# ProProject_Turbo_Drive_2024-05-30.net
KiCad netlist of a schematic drawn in EasyEDA Pro
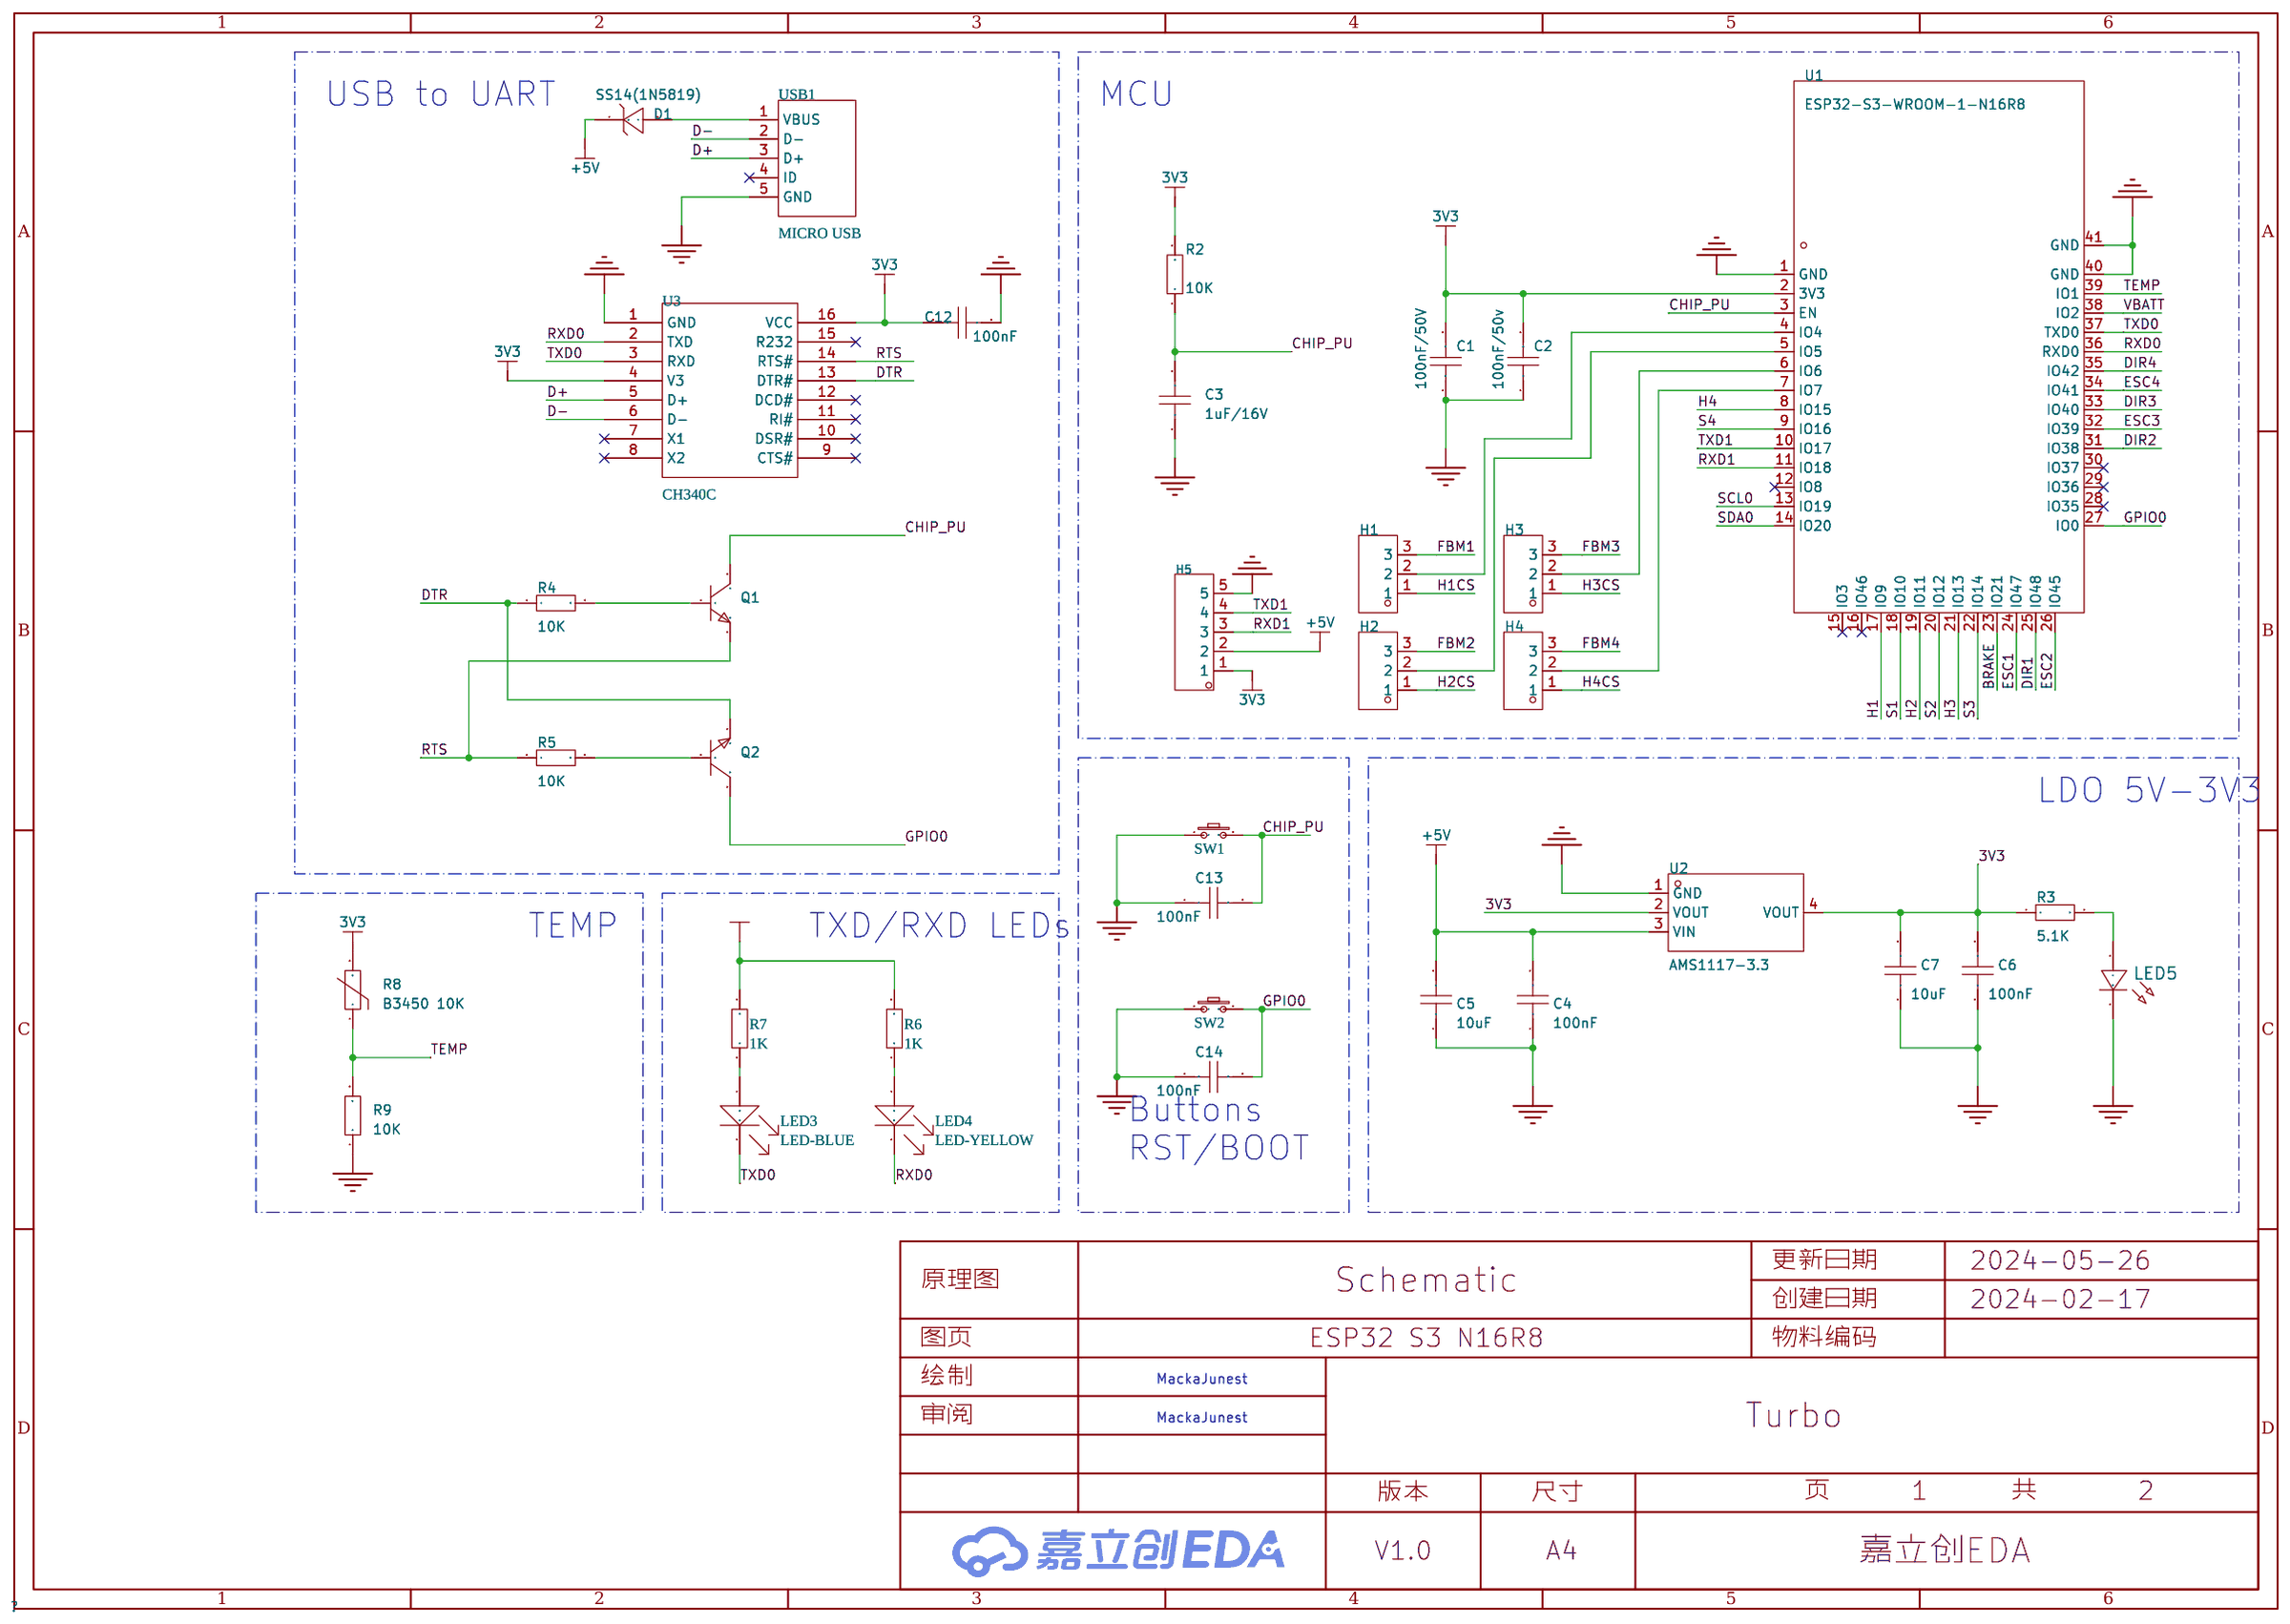
[diagram p0: ESP32 S3 N16R8]
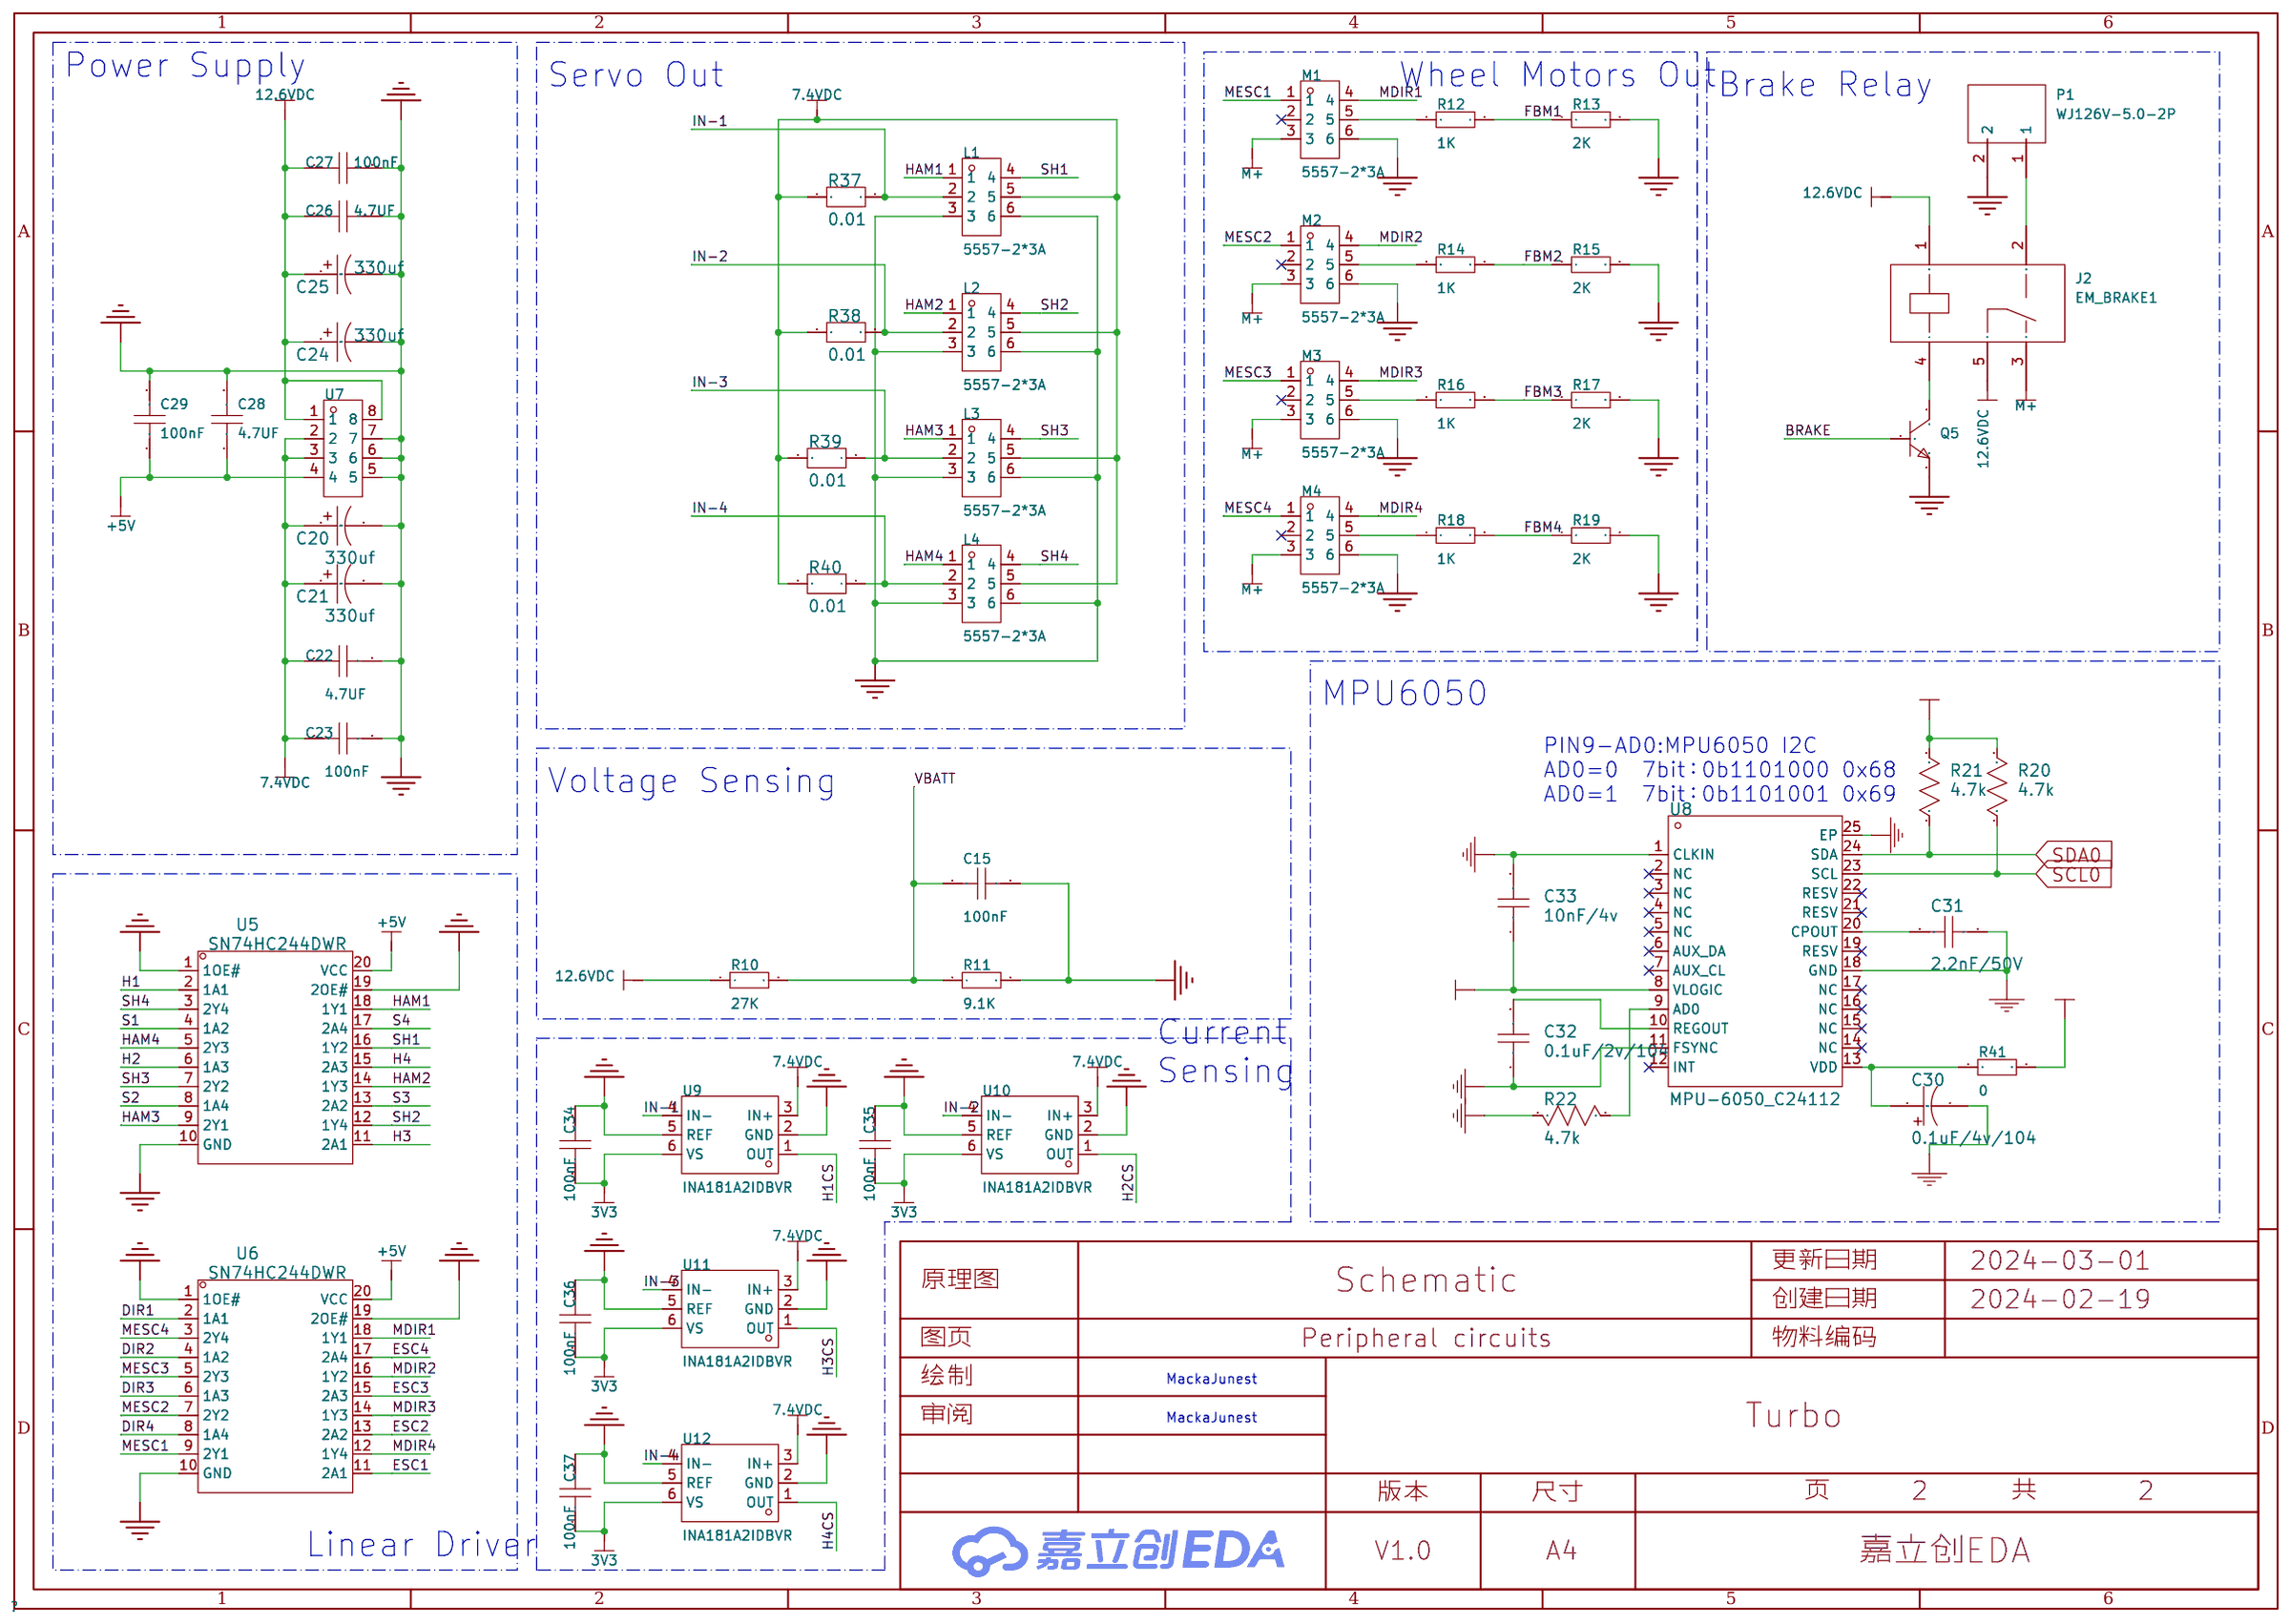
[diagram p1: Peripheral circuits]

(export (version "E")
  (design (tool "Eeschema 10.0.6"))
  (components
    (comp (ref "C1")
      (value "100nF/50V")
      (footprint "easyedapro:C0603")
      (libsource (lib "easyedapro") (part "CapAcitance"))
    )
    (comp (ref "C2")
      (value "100nF/50v")
      (footprint "easyedapro:C0603")
      (libsource (lib "easyedapro") (part "CapAcitance"))
    )
    (comp (ref "C3")
      (value "1uF/16V")
      (footprint "easyedapro:C0603")
      (libsource (lib "easyedapro") (part "CapAcitance"))
    )
    (comp (ref "C4")
      (value "100nF")
      (footprint "easyedapro:C0603")
      (libsource (lib "easyedapro") (part "CapAcitance"))
    )
    (comp (ref "C5")
      (value "10uF")
      (footprint "easyedapro:C0603")
      (libsource (lib "easyedapro") (part "CapAcitance"))
    )
    (comp (ref "C6")
      (value "100nF")
      (footprint "easyedapro:C0603")
      (libsource (lib "easyedapro") (part "CapAcitance"))
    )
    (comp (ref "C7")
      (value "10uF")
      (footprint "easyedapro:C0603")
      (libsource (lib "easyedapro") (part "CapAcitance"))
    )
    (comp (ref "C12")
      (value "100nF")
      (footprint "easyedapro:C0603")
      (libsource (lib "easyedapro") (part "CapAcitance"))
    )
    (comp (ref "C13")
      (value "100nF")
      (footprint "easyedapro:C0603")
      (libsource (lib "easyedapro") (part "CapAcitance"))
    )
    (comp (ref "C14")
      (value "100nF")
      (footprint "easyedapro:C0603")
      (libsource (lib "easyedapro") (part "CapAcitance"))
    )
    (comp (ref "D1")
      (value "SS14(1N5819)")
      (footprint "easyedapro:SMA_L4.3-W2.7-LS5.1-RD")
      (libsource (lib "easyedapro") (part "SS14(1N5819)-SMA"))
    )
    (comp (ref "H1")
      (value "~")
      (footprint "easyedapro:HDR-TH_3P-P2.54-V-M")
      (libsource (lib "easyedapro") (part "PZ254V-11-03P_C2937625"))
    )
    (comp (ref "H2")
      (value "~")
      (footprint "easyedapro:HDR-TH_3P-P2.54-V-M")
      (libsource (lib "easyedapro") (part "PZ254V-11-03P_C2937625"))
    )
    (comp (ref "H3")
      (value "~")
      (footprint "easyedapro:HDR-TH_3P-P2.54-V-M")
      (libsource (lib "easyedapro") (part "PZ254V-11-03P_C2937625"))
    )
    (comp (ref "H4")
      (value "~")
      (footprint "easyedapro:HDR-TH_3P-P2.54-V-M")
      (libsource (lib "easyedapro") (part "PZ254V-11-03P_C2937625"))
    )
    (comp (ref "H5")
      (value "~")
      (footprint "easyedapro:HDR-TH_5P-P2.54-V-M")
      (libsource (lib "easyedapro") (part "MTP125-1105S1"))
    )
    (comp (ref "LED3")
      (value "LED-BLUE")
      (footprint "easyedapro:LED 0805B")
      (libsource (lib "easyedapro") (part "LED-BLUE"))
    )
    (comp (ref "LED4")
      (value "LED-YELLOW")
      (footprint "easyedapro:LED 0805Y")
      (libsource (lib "easyedapro") (part "LED-YELLOW"))
    )
    (comp (ref "LED5")
      (value "~")
      (footprint "easyedapro:LED_0603")
      (libsource (lib "easyedapro") (part "LED_R"))
    )
    (comp (ref "Q1")
      (value "~")
      (footprint "easyedapro:S8050_SOT-23")
      (libsource (lib "easyedapro") (part "NPN"))
    )
    (comp (ref "Q2")
      (value "~")
      (footprint "easyedapro:S8050_SOT-23")
      (libsource (lib "easyedapro") (part "NPN"))
    )
    (comp (ref "R2") (value "10K") (footprint "easyedapro:R0603") (libsource (lib "easyedapro") (part "电阻")))
    (comp (ref "R3") (value "5.1K") (footprint "easyedapro:R0603") (libsource (lib "easyedapro") (part "电阻")))
    (comp (ref "R4") (value "10K") (footprint "easyedapro:R0603") (libsource (lib "easyedapro") (part "电阻")))
    (comp (ref "R5") (value "10K") (footprint "easyedapro:R0603") (libsource (lib "easyedapro") (part "电阻")))
    (comp (ref "R6")
      (value "1K")
      (footprint "easyedapro:R 0603_L")
      (libsource (lib "easyedapro") (part "1K"))
    )
    (comp (ref "R7")
      (value "1K")
      (footprint "easyedapro:R 0603_L")
      (libsource (lib "easyedapro") (part "1K"))
    )
    (comp (ref "R8")
      (value "B3450 10K")
      (footprint "easyedapro:R0603")
      (description "阻值(25°C):10kΩ;B值(25°C/50°C):3950K;电阻精度:±1%;功率:100mW;B值精度:±1%;最大稳态电流(25°C):310uA;")
      (fields (field (name "Manufacturer") "KUU"))
      (libsource (lib "easyedapro") (part "KNTC0603/10KF3950"))
    )
    (comp (ref "R9") (value "10K") (footprint "easyedapro:R0603") (libsource (lib "easyedapro") (part "电阻")))
    (comp (ref "SW1")
      (value "3x6x5")
      (footprint "easyedapro:TSW SMD-3*6*2.5")
      (libsource (lib "easyedapro") (part "3x6x5"))
    )
    (comp (ref "SW2")
      (value "3x6x5")
      (footprint "easyedapro:TSW SMD-3*6*2.5")
      (libsource (lib "easyedapro") (part "3x6x5"))
    )
    (comp (ref "U1")
      (value "ESP32-S3-WROOM-1-N16R8")
      (footprint "easyedapro:WIRELM-SMD_ESP32-S3-WROOM-1")
      (fields (field (name "Manufacturer") "ESPRESSIF(乐鑫)"))
      (libsource (lib "easyedapro") (part "ESP32-S3-WROOM-1(N16R8)"))
    )
    (comp (ref "U2")
      (value "AMS1117-3.3")
      (footprint "easyedapro:SOT-223-3_L6.5-W3.4-P2.30-LS7.0-BR")
      (description "输出类型:固定;最大输入电压:-;输出电压:3.3V;最大输出电流:1A;电源纹波抑制比(PSRR):72dB@(120Hz);输出极性:正极;")
      (fields (field (name "Manufacturer") "AMS"))
      (libsource (lib "easyedapro") (part "AMS1117-3.3"))
    )
    (comp (ref "U3")
      (value "CH340C")
      (footprint "easyedapro:SOP16_L")
      (libsource (lib "easyedapro") (part "CH340C"))
    )
    (comp (ref "USB1")
      (value "MICRO USB")
      (footprint "easyedapro:USB-MICRO_B")
      (libsource (lib "easyedapro") (part "MICRO USB"))
    )
    (comp (ref "C15")
      (value "100nF")
      (footprint "easyedapro:C0603")
      (libsource (lib "easyedapro") (part "CapAcitance"))
    )
    (comp (ref "C20")
      (value "330uf")
      (footprint "easyedapro:CAP-T-10*10.5")
      (libsource (lib "easyedapro") (part "330uf"))
    )
    (comp (ref "C21")
      (value "330uf")
      (footprint "easyedapro:CAP-T-10*10.5")
      (libsource (lib "easyedapro") (part "330uf"))
    )
    (comp (ref "C22")
      (value "4.7UF")
      (footprint "easyedapro:C0603")
      (libsource (lib "easyedapro") (part "CapAcitance"))
    )
    (comp (ref "C23")
      (value "100nF")
      (footprint "easyedapro:C0603")
      (libsource (lib "easyedapro") (part "CapAcitance"))
    )
    (comp (ref "C24")
      (value "330uf")
      (footprint "easyedapro:CAP-T-10*10.5")
      (libsource (lib "easyedapro") (part "330uf"))
    )
    (comp (ref "C25")
      (value "330uf")
      (footprint "easyedapro:CAP-T-10*10.5")
      (libsource (lib "easyedapro") (part "330uf"))
    )
    (comp (ref "C26")
      (value "4.7UF")
      (footprint "easyedapro:C0603")
      (libsource (lib "easyedapro") (part "CapAcitance"))
    )
    (comp (ref "C27")
      (value "100nF")
      (footprint "easyedapro:C0603")
      (libsource (lib "easyedapro") (part "CapAcitance"))
    )
    (comp (ref "C28")
      (value "4.7UF")
      (footprint "easyedapro:C0603")
      (libsource (lib "easyedapro") (part "CapAcitance"))
    )
    (comp (ref "C29")
      (value "100nF")
      (footprint "easyedapro:C0603")
      (libsource (lib "easyedapro") (part "CapAcitance"))
    )
    (comp (ref "C30")
      (value "0.1uF/4v/104")
      (fields (field (name "Manufacturer Part") "TPSA106K016R1000") (field (name "Manufacturer") "AVX"))
      (libsource (lib "easyedapro") (part "0.1uF/4v/104"))
    )
    (comp (ref "C31") (value "2.2nF/50V") (libsource (lib "easyedapro") (part "2.2nF/50V")))
    (comp (ref "C32") (value "0.1uF/2v/104") (libsource (lib "easyedapro") (part "0.1uF/2v/104")))
    (comp (ref "C33") (value "10nF/4v") (libsource (lib "easyedapro") (part "10nF/4v")))
    (comp (ref "C34")
      (value "100nF")
      (footprint "easyedapro:C0603")
      (libsource (lib "easyedapro") (part "CapAcitance"))
    )
    (comp (ref "C35")
      (value "100nF")
      (footprint "easyedapro:C0603")
      (libsource (lib "easyedapro") (part "CapAcitance"))
    )
    (comp (ref "C36")
      (value "100nF")
      (footprint "easyedapro:C0603")
      (libsource (lib "easyedapro") (part "CapAcitance"))
    )
    (comp (ref "C37")
      (value "100nF")
      (footprint "easyedapro:C0603")
      (libsource (lib "easyedapro") (part "CapAcitance"))
    )
    (comp (ref "J2")
      (value "EM_BRAKE1")
      (footprint "easyedapro:RELAY-TH_SRD-XXVDC-XL-C")
      (description "线圈电压:12V;触点形式:一组转换:1C(单刀双掷-转换);触点容量(电阻负载):-;最大切换电压:250V@AC;最大切换电流:15A;")
      (fields (field (name "Manufacturer Part") "SRD-12VDC-SL-C") (field (name "Manufacturer") "松乐"))
      (libsource (lib "easyedapro") (part "SRD-12VDC-SL-C"))
    )
    (comp (ref "L1")
      (value "5557-2*3A")
      (footprint "easyedapro:CONN-TH_5557-2X3A")
      (fields (field (name "Manufacturer") "FG(富港)"))
      (libsource (lib "easyedapro") (part "5557-2*3A"))
    )
    (comp (ref "L2")
      (value "5557-2*3A")
      (footprint "easyedapro:CONN-TH_5557-2X3A")
      (fields (field (name "Manufacturer") "FG(富港)"))
      (libsource (lib "easyedapro") (part "5557-2*3A"))
    )
    (comp (ref "L3")
      (value "5557-2*3A")
      (footprint "easyedapro:CONN-TH_5557-2X3A")
      (fields (field (name "Manufacturer") "FG(富港)"))
      (libsource (lib "easyedapro") (part "5557-2*3A"))
    )
    (comp (ref "L4")
      (value "5557-2*3A")
      (footprint "easyedapro:CONN-TH_5557-2X3A")
      (fields (field (name "Manufacturer") "FG(富港)"))
      (libsource (lib "easyedapro") (part "5557-2*3A"))
    )
    (comp (ref "M1")
      (value "5557-2*3A")
      (footprint "easyedapro:CONN-TH_5557-2X3A")
      (fields (field (name "Manufacturer") "FG(富港)"))
      (libsource (lib "easyedapro") (part "5557-2*3A"))
    )
    (comp (ref "M2")
      (value "5557-2*3A")
      (footprint "easyedapro:CONN-TH_5557-2X3A")
      (fields (field (name "Manufacturer") "FG(富港)"))
      (libsource (lib "easyedapro") (part "5557-2*3A"))
    )
    (comp (ref "M3")
      (value "5557-2*3A")
      (footprint "easyedapro:CONN-TH_5557-2X3A")
      (fields (field (name "Manufacturer") "FG(富港)"))
      (libsource (lib "easyedapro") (part "5557-2*3A"))
    )
    (comp (ref "M4")
      (value "5557-2*3A")
      (footprint "easyedapro:CONN-TH_5557-2X3A")
      (fields (field (name "Manufacturer") "FG(富港)"))
      (libsource (lib "easyedapro") (part "5557-2*3A"))
    )
    (comp (ref "P1")
      (value "WJ126V-5.0-2P")
      (footprint "easyedapro:CONN-TH_WJ126V-5.0-2P")
      (fields (field (name "Manufacturer") "KANGNEX(康奈克斯电气)"))
      (libsource (lib "easyedapro") (part "WJ126V-5.0-2P"))
    )
    (comp (ref "Q5")
      (value "~")
      (footprint "easyedapro:S8050_SOT-23")
      (libsource (lib "easyedapro") (part "NPN"))
    )
    (comp (ref "R10") (value "27K") (footprint "easyedapro:R0603") (libsource (lib "easyedapro") (part "电阻")))
    (comp (ref "R11")
      (value "9.1K")
      (footprint "easyedapro:R0603")
      (libsource (lib "easyedapro") (part "电阻"))
    )
    (comp (ref "R12") (value "1K") (footprint "easyedapro:R0603") (libsource (lib "easyedapro") (part "电阻")))
    (comp (ref "R13") (value "2K") (footprint "easyedapro:R0603") (libsource (lib "easyedapro") (part "电阻")))
    (comp (ref "R14") (value "1K") (footprint "easyedapro:R0603") (libsource (lib "easyedapro") (part "电阻")))
    (comp (ref "R15") (value "2K") (footprint "easyedapro:R0603") (libsource (lib "easyedapro") (part "电阻")))
    (comp (ref "R16") (value "1K") (footprint "easyedapro:R0603") (libsource (lib "easyedapro") (part "电阻")))
    (comp (ref "R17") (value "2K") (footprint "easyedapro:R0603") (libsource (lib "easyedapro") (part "电阻")))
    (comp (ref "R18") (value "1K") (footprint "easyedapro:R0603") (libsource (lib "easyedapro") (part "电阻")))
    (comp (ref "R19") (value "2K") (footprint "easyedapro:R0603") (libsource (lib "easyedapro") (part "电阻")))
    (comp (ref "R20") (value "4.7k") (libsource (lib "easyedapro") (part "4.7k")))
    (comp (ref "R21") (value "4.7k") (libsource (lib "easyedapro") (part "4.7k")))
    (comp (ref "R22") (value "4.7k") (libsource (lib "") (part "4.7k_1")))
    (comp (ref "R37")
      (value "0.01")
      (footprint "easyedapro:R2512")
      (libsource (lib "easyedapro") (part "0.01"))
    )
    (comp (ref "R38")
      (value "0.01")
      (footprint "easyedapro:R2512")
      (libsource (lib "easyedapro") (part "0.01"))
    )
    (comp (ref "R39")
      (value "0.01")
      (footprint "easyedapro:R2512")
      (libsource (lib "easyedapro") (part "0.01"))
    )
    (comp (ref "R40")
      (value "0.01")
      (footprint "easyedapro:R2512")
      (libsource (lib "easyedapro") (part "0.01"))
    )
    (comp (ref "R41") (value "0") (footprint "easyedapro:R0603") (libsource (lib "easyedapro") (part "电阻")))
    (comp (ref "U5")
      (value "SN74HC244DWR")
      (footprint "easyedapro:SOIC-20_L13.0-W7.6-P1.27-LS10.6-BL")
      (fields (field (name "Manufacturer Part") "SN74AHC244DWR") (field (name "Manufacturer") "TI"))
      (libsource (lib "easyedapro") (part "SN74HC244DWR"))
    )
    (comp (ref "U6")
      (value "SN74HC244DWR")
      (footprint "easyedapro:SOIC-20_L13.0-W7.6-P1.27-LS10.6-BL")
      (fields (field (name "Manufacturer Part") "SN74AHC244DWR") (field (name "Manufacturer") "TI"))
      (libsource (lib "easyedapro") (part "SN74HC244DWR"))
    )
    (comp (ref "U7")
      (value "5557-2*4P直针座-黑色8芯")
      (footprint "easyedapro:CONN-TH_5557-2-4P")
      (libsource (lib "easyedapro") (part "5557-2*4P直针座-黑色8芯"))
    )
    (comp (ref "U8")
      (value "MPU-6050_C24112")
      (fields (field (name "Manufacturer Part") "MPU-6050") (field (name "Manufacturer") "InvenSense"))
      (libsource (lib "easyedapro") (part "MPU-6050_C24112"))
    )
    (comp (ref "U9")
      (value "INA181A2IDBVR")
      (footprint "easyedapro:SOT-23-6_L2.9-W1.6-P0.95-LS2.8-BL")
      (description "放大器数:单路;")
      (fields (field (name "Manufacturer") "TI(德州仪器)"))
      (libsource (lib "easyedapro") (part "INA181A2IDBVR"))
    )
    (comp (ref "U10")
      (value "INA181A2IDBVR")
      (footprint "easyedapro:SOT-23-6_L2.9-W1.6-P0.95-LS2.8-BL")
      (description "放大器数:单路;")
      (fields (field (name "Manufacturer") "TI(德州仪器)"))
      (libsource (lib "easyedapro") (part "INA181A2IDBVR"))
    )
    (comp (ref "U11")
      (value "INA181A2IDBVR")
      (footprint "easyedapro:SOT-23-6_L2.9-W1.6-P0.95-LS2.8-BL")
      (description "放大器数:单路;")
      (fields (field (name "Manufacturer") "TI(德州仪器)"))
      (libsource (lib "easyedapro") (part "INA181A2IDBVR"))
    )
    (comp (ref "U12")
      (value "INA181A2IDBVR")
      (footprint "easyedapro:SOT-23-6_L2.9-W1.6-P0.95-LS2.8-BL")
      (description "放大器数:单路;")
      (fields (field (name "Manufacturer") "TI(德州仪器)"))
      (libsource (lib "easyedapro") (part "INA181A2IDBVR"))
    )
  )
  (nets
    (net (code "1") (name "+5V") (class "Default")
      (node (ref "C28") (pin "1") (pinfunction "1_1") (pintype "input"))
      (node (ref "C29") (pin "1") (pinfunction "1_1") (pintype "input"))
      (node (ref "C4") (pin "2") (pinfunction "2_2") (pintype "input"))
      (node (ref "C5") (pin "2") (pinfunction "2_2") (pintype "input"))
      (node (ref "D1") (pin "1") (pinfunction "C_1") (pintype "input"))
      (node (ref "H5") (pin "2") (pinfunction "2_2") (pintype "input"))
      (node (ref "U2") (pin "3") (pinfunction "VIN_3") (pintype "unspecified"))
      (node (ref "U5") (pin "20") (pinfunction "VCC_20") (pintype "input"))
      (node (ref "U6") (pin "20") (pinfunction "VCC_20") (pintype "input"))
      (node (ref "U7") (pin "4") (pinfunction "4_4") (pintype "input"))
    )
    (net (code "2") (name "3V3") (class "Default")
      (node (ref "C1") (pin "2") (pinfunction "2_2") (pintype "input"))
      (node (ref "C12") (pin "1") (pinfunction "1_1") (pintype "input"))
      (node (ref "C2") (pin "2") (pinfunction "2_2") (pintype "input"))
      (node (ref "C33") (pin "1") (pinfunction "1_1") (pintype "input"))
      (node (ref "C34") (pin "1") (pinfunction "1_1") (pintype "input"))
      (node (ref "C35") (pin "1") (pinfunction "1_1") (pintype "input"))
      (node (ref "C36") (pin "1") (pinfunction "1_1") (pintype "input"))
      (node (ref "C37") (pin "1") (pinfunction "1_1") (pintype "input"))
      (node (ref "C6") (pin "2") (pinfunction "2_2") (pintype "input"))
      (node (ref "C7") (pin "2") (pinfunction "2_2") (pintype "input"))
      (node (ref "H5") (pin "1") (pinfunction "1_1") (pintype "input"))
      (node (ref "R2") (pin "2") (pinfunction "2_2") (pintype "input"))
      (node (ref "R20") (pin "2") (pinfunction "2_2") (pintype "input"))
      (node (ref "R21") (pin "2") (pinfunction "2_2") (pintype "input"))
      (node (ref "R3") (pin "1") (pinfunction "1_1") (pintype "input"))
      (node (ref "R41") (pin "2") (pinfunction "2_2") (pintype "input"))
      (node (ref "R6") (pin "2") (pinfunction "2_2") (pintype "input"))
      (node (ref "R7") (pin "2") (pinfunction "2_2") (pintype "input"))
      (node (ref "R8") (pin "2") (pinfunction "2_2") (pintype "unspecified"))
      (node (ref "U1") (pin "2") (pinfunction "3V3_2") (pintype "unspecified"))
      (node (ref "U10") (pin "6") (pinfunction "VS_6") (pintype "input"))
      (node (ref "U11") (pin "6") (pinfunction "VS_6") (pintype "input"))
      (node (ref "U12") (pin "6") (pinfunction "VS_6") (pintype "input"))
      (node (ref "U2") (pin "2") (pinfunction "VOUT_2") (pintype "unspecified"))
      (node (ref "U2") (pin "4") (pinfunction "VOUT_4") (pintype "unspecified"))
      (node (ref "U3") (pin "16") (pinfunction "VCC_16") (pintype "input"))
      (node (ref "U3") (pin "4") (pinfunction "V3_4") (pintype "input"))
      (node (ref "U8") (pin "8") (pinfunction "VLOGIC_8") (pintype "input"))
      (node (ref "U9") (pin "6") (pinfunction "VS_6") (pintype "input"))
    )
    (net (code "3") (name "7.4VDC") (class "Default")
      (node (ref "C20") (pin "1") (pinfunction "1_1") (pintype "input"))
      (node (ref "C21") (pin "1") (pinfunction "1_1") (pintype "input"))
      (node (ref "C22") (pin "1") (pinfunction "1_1") (pintype "input"))
      (node (ref "C23") (pin "1") (pinfunction "1_1") (pintype "input"))
      (node (ref "L1") (pin "5") (pinfunction "5_5") (pintype "input"))
      (node (ref "L2") (pin "5") (pinfunction "5_5") (pintype "input"))
      (node (ref "L3") (pin "5") (pinfunction "5_5") (pintype "input"))
      (node (ref "L4") (pin "5") (pinfunction "5_5") (pintype "input"))
      (node (ref "R37") (pin "2") (pinfunction "2_2") (pintype "input"))
      (node (ref "R38") (pin "2") (pinfunction "2_2") (pintype "input"))
      (node (ref "R39") (pin "2") (pinfunction "2_2") (pintype "input"))
      (node (ref "R40") (pin "2") (pinfunction "2_2") (pintype "input"))
      (node (ref "U10") (pin "3") (pinfunction "IN+_3") (pintype "input"))
      (node (ref "U11") (pin "3") (pinfunction "IN+_3") (pintype "input"))
      (node (ref "U12") (pin "3") (pinfunction "IN+_3") (pintype "input"))
      (node (ref "U7") (pin "2") (pinfunction "2_2") (pintype "input"))
      (node (ref "U7") (pin "3") (pinfunction "3_3") (pintype "input"))
      (node (ref "U9") (pin "3") (pinfunction "IN+_3") (pintype "input"))
    )
    (net (code "4") (name "12.6VDC") (class "Default")
      (node (ref "C24") (pin "1") (pinfunction "1_1") (pintype "input"))
      (node (ref "C25") (pin "1") (pinfunction "1_1") (pintype "input"))
      (node (ref "C26") (pin "1") (pinfunction "1_1") (pintype "input"))
      (node (ref "C27") (pin "1") (pinfunction "1_1") (pintype "input"))
      (node (ref "J2") (pin "1") (pinfunction "1_1") (pintype "input"))
      (node (ref "J2") (pin "5") (pinfunction "5_5") (pintype "input"))
      (node (ref "R10") (pin "1") (pinfunction "1_1") (pintype "input"))
      (node (ref "U7") (pin "1") (pinfunction "1_1") (pintype "input"))
      (node (ref "U7") (pin "8") (pinfunction "8_8") (pintype "input"))
    )
    (net (code "5") (name "BRAKE") (class "Default")
      (node (ref "Q5") (pin "1") (pinfunction "1_1") (pintype "unspecified"))
      (node (ref "U1") (pin "23") (pinfunction "IO21_23") (pintype "unspecified"))
    )
    (net (code "6") (name "CHIP_PU") (class "Default")
      (node (ref "C13") (pin "2") (pinfunction "2_2") (pintype "input"))
      (node (ref "C3") (pin "2") (pinfunction "2_2") (pintype "input"))
      (node (ref "Q1") (pin "3") (pinfunction "3_3") (pintype "unspecified"))
      (node (ref "R2") (pin "1") (pinfunction "1_1") (pintype "input"))
      (node (ref "SW1") (pin "2") (pinfunction "2_2") (pintype "input"))
      (node (ref "U1") (pin "3") (pinfunction "EN_3") (pintype "unspecified"))
    )
    (net (code "7") (name "D+") (class "Default")
      (node (ref "U3") (pin "5") (pinfunction "D+_5") (pintype "input"))
      (node (ref "USB1") (pin "3") (pinfunction "D+_3") (pintype "input"))
    )
    (net (code "8") (name "D-") (class "Default")
      (node (ref "U3") (pin "6") (pinfunction "D-_6") (pintype "input"))
      (node (ref "USB1") (pin "2") (pinfunction "D-_2") (pintype "input"))
    )
    (net (code "9") (name "DIR1") (class "Default")
      (node (ref "U1") (pin "25") (pinfunction "IO48_25") (pintype "unspecified"))
      (node (ref "U6") (pin "2") (pinfunction "1A1_2") (pintype "input"))
    )
    (net (code "10") (name "DIR2") (class "Default")
      (node (ref "U1") (pin "31") (pinfunction "IO38_31") (pintype "unspecified"))
      (node (ref "U6") (pin "4") (pinfunction "1A2_4") (pintype "input"))
    )
    (net (code "11") (name "DIR3") (class "Default")
      (node (ref "U1") (pin "33") (pinfunction "IO40_33") (pintype "unspecified"))
      (node (ref "U6") (pin "6") (pinfunction "1A3_6") (pintype "input"))
    )
    (net (code "12") (name "DIR4") (class "Default")
      (node (ref "U1") (pin "35") (pinfunction "IO42_35") (pintype "unspecified"))
      (node (ref "U6") (pin "8") (pinfunction "1A4_8") (pintype "input"))
    )
    (net (code "13") (name "DTR") (class "Default")
      (node (ref "Q2") (pin "2") (pinfunction "2_2") (pintype "unspecified"))
      (node (ref "R4") (pin "1") (pinfunction "1_1") (pintype "input"))
      (node (ref "U3") (pin "13") (pinfunction "DTR#_13") (pintype "input"))
    )
    (net (code "14") (name "ESC1") (class "Default")
      (node (ref "U1") (pin "24") (pinfunction "IO47_24") (pintype "unspecified"))
      (node (ref "U6") (pin "11") (pinfunction "2A1_11") (pintype "input"))
    )
    (net (code "15") (name "ESC2") (class "Default")
      (node (ref "U1") (pin "26") (pinfunction "IO45_26") (pintype "unspecified"))
      (node (ref "U6") (pin "13") (pinfunction "2A2_13") (pintype "input"))
    )
    (net (code "16") (name "ESC3") (class "Default")
      (node (ref "U1") (pin "32") (pinfunction "IO39_32") (pintype "unspecified"))
      (node (ref "U6") (pin "15") (pinfunction "2A3_15") (pintype "input"))
    )
    (net (code "17") (name "ESC4") (class "Default")
      (node (ref "U1") (pin "34") (pinfunction "IO41_34") (pintype "unspecified"))
      (node (ref "U6") (pin "17") (pinfunction "2A4_17") (pintype "input"))
    )
    (net (code "18") (name "FBM1") (class "Default")
      (node (ref "H1") (pin "3") (pinfunction "3_3") (pintype "input"))
      (node (ref "R12") (pin "2") (pinfunction "2_2") (pintype "input"))
      (node (ref "R13") (pin "1") (pinfunction "1_1") (pintype "input"))
    )
    (net (code "19") (name "FBM2") (class "Default")
      (node (ref "H2") (pin "3") (pinfunction "3_3") (pintype "input"))
      (node (ref "R14") (pin "2") (pinfunction "2_2") (pintype "input"))
      (node (ref "R15") (pin "1") (pinfunction "1_1") (pintype "input"))
    )
    (net (code "20") (name "FBM3") (class "Default")
      (node (ref "H3") (pin "3") (pinfunction "3_3") (pintype "input"))
      (node (ref "R16") (pin "2") (pinfunction "2_2") (pintype "input"))
      (node (ref "R17") (pin "1") (pinfunction "1_1") (pintype "input"))
    )
    (net (code "21") (name "FBM4") (class "Default")
      (node (ref "H4") (pin "3") (pinfunction "3_3") (pintype "input"))
      (node (ref "R18") (pin "2") (pinfunction "2_2") (pintype "input"))
      (node (ref "R19") (pin "1") (pinfunction "1_1") (pintype "input"))
    )
    (net (code "22") (name "GND") (class "Default")
      (node (ref "C1") (pin "1") (pinfunction "1_1") (pintype "input"))
      (node (ref "C12") (pin "2") (pinfunction "2_2") (pintype "input"))
      (node (ref "C13") (pin "1") (pinfunction "1_1") (pintype "input"))
      (node (ref "C14") (pin "1") (pinfunction "1_1") (pintype "input"))
      (node (ref "C15") (pin "2") (pinfunction "2_2") (pintype "input"))
      (node (ref "C2") (pin "1") (pinfunction "1_1") (pintype "input"))
      (node (ref "C20") (pin "2") (pinfunction "2_2") (pintype "input"))
      (node (ref "C21") (pin "2") (pinfunction "2_2") (pintype "input"))
      (node (ref "C22") (pin "2") (pinfunction "2_2") (pintype "input"))
      (node (ref "C23") (pin "2") (pinfunction "2_2") (pintype "input"))
      (node (ref "C24") (pin "2") (pinfunction "2_2") (pintype "input"))
      (node (ref "C25") (pin "2") (pinfunction "2_2") (pintype "input"))
      (node (ref "C26") (pin "2") (pinfunction "2_2") (pintype "input"))
      (node (ref "C27") (pin "2") (pinfunction "2_2") (pintype "input"))
      (node (ref "C28") (pin "2") (pinfunction "2_2") (pintype "input"))
      (node (ref "C29") (pin "2") (pinfunction "2_2") (pintype "input"))
      (node (ref "C3") (pin "1") (pinfunction "1_1") (pintype "input"))
      (node (ref "C30") (pin "2") (pinfunction "2_2") (pintype "input"))
      (node (ref "C31") (pin "1") (pinfunction "1_1") (pintype "input"))
      (node (ref "C32") (pin "1") (pinfunction "1_1") (pintype "input"))
      (node (ref "C33") (pin "2") (pinfunction "2_2") (pintype "input"))
      (node (ref "C34") (pin "2") (pinfunction "2_2") (pintype "input"))
      (node (ref "C35") (pin "2") (pinfunction "2_2") (pintype "input"))
      (node (ref "C36") (pin "2") (pinfunction "2_2") (pintype "input"))
      (node (ref "C37") (pin "2") (pinfunction "2_2") (pintype "input"))
      (node (ref "C4") (pin "1") (pinfunction "1_1") (pintype "input"))
      (node (ref "C5") (pin "1") (pinfunction "1_1") (pintype "input"))
      (node (ref "C6") (pin "1") (pinfunction "1_1") (pintype "input"))
      (node (ref "C7") (pin "1") (pinfunction "1_1") (pintype "input"))
      (node (ref "H5") (pin "5") (pinfunction "5_5") (pintype "input"))
      (node (ref "L1") (pin "3") (pinfunction "3_3") (pintype "input"))
      (node (ref "L1") (pin "6") (pinfunction "6_6") (pintype "input"))
      (node (ref "L2") (pin "3") (pinfunction "3_3") (pintype "input"))
      (node (ref "L2") (pin "6") (pinfunction "6_6") (pintype "input"))
      (node (ref "L3") (pin "3") (pinfunction "3_3") (pintype "input"))
      (node (ref "L3") (pin "6") (pinfunction "6_6") (pintype "input"))
      (node (ref "L4") (pin "3") (pinfunction "3_3") (pintype "input"))
      (node (ref "L4") (pin "6") (pinfunction "6_6") (pintype "input"))
      (node (ref "LED5") (pin "1") (pinfunction "C_1") (pintype "input"))
      (node (ref "M1") (pin "6") (pinfunction "6_6") (pintype "input"))
      (node (ref "M2") (pin "6") (pinfunction "6_6") (pintype "input"))
      (node (ref "M3") (pin "6") (pinfunction "6_6") (pintype "input"))
      (node (ref "M4") (pin "6") (pinfunction "6_6") (pintype "input"))
      (node (ref "P1") (pin "2") (pinfunction "2_2") (pintype "input"))
      (node (ref "Q5") (pin "2") (pinfunction "2_2") (pintype "unspecified"))
      (node (ref "R11") (pin "2") (pinfunction "2_2") (pintype "input"))
      (node (ref "R13") (pin "2") (pinfunction "2_2") (pintype "input"))
      (node (ref "R15") (pin "2") (pinfunction "2_2") (pintype "input"))
      (node (ref "R17") (pin "2") (pinfunction "2_2") (pintype "input"))
      (node (ref "R19") (pin "2") (pinfunction "2_2") (pintype "input"))
      (node (ref "R22") (pin "1") (pinfunction "1_1") (pintype "input"))
      (node (ref "R9") (pin "1") (pinfunction "1_1") (pintype "input"))
      (node (ref "SW1") (pin "1") (pinfunction "1_1") (pintype "input"))
      (node (ref "SW2") (pin "1") (pinfunction "1_1") (pintype "input"))
      (node (ref "U1") (pin "1") (pinfunction "GND_1") (pintype "unspecified"))
      (node (ref "U1") (pin "40") (pinfunction "GND_40") (pintype "unspecified"))
      (node (ref "U1") (pin "41") (pinfunction "GND_41") (pintype "unspecified"))
      (node (ref "U10") (pin "2") (pinfunction "GND_2") (pintype "input"))
      (node (ref "U10") (pin "5") (pinfunction "REF_5") (pintype "input"))
      (node (ref "U11") (pin "2") (pinfunction "GND_2") (pintype "input"))
      (node (ref "U11") (pin "5") (pinfunction "REF_5") (pintype "input"))
      (node (ref "U12") (pin "2") (pinfunction "GND_2") (pintype "input"))
      (node (ref "U12") (pin "5") (pinfunction "REF_5") (pintype "input"))
      (node (ref "U2") (pin "1") (pinfunction "GND_1") (pintype "unspecified"))
      (node (ref "U3") (pin "1") (pinfunction "GND_1") (pintype "input"))
      (node (ref "U5") (pin "1") (pinfunction "1OE#_1") (pintype "input"))
      (node (ref "U5") (pin "10") (pinfunction "GND_10") (pintype "input"))
      (node (ref "U5") (pin "19") (pinfunction "2OE#_19") (pintype "input"))
      (node (ref "U6") (pin "1") (pinfunction "1OE#_1") (pintype "input"))
      (node (ref "U6") (pin "10") (pinfunction "GND_10") (pintype "input"))
      (node (ref "U6") (pin "19") (pinfunction "2OE#_19") (pintype "input"))
      (node (ref "U7") (pin "5") (pinfunction "5_5") (pintype "input"))
      (node (ref "U7") (pin "6") (pinfunction "6_6") (pintype "input"))
      (node (ref "U7") (pin "7") (pinfunction "7_7") (pintype "input"))
      (node (ref "U8") (pin "1") (pinfunction "CLKIN_1") (pintype "input"))
      (node (ref "U8") (pin "11") (pinfunction "FSYNC_11") (pintype "input"))
      (node (ref "U8") (pin "18") (pinfunction "GND_18") (pintype "input"))
      (node (ref "U8") (pin "25") (pinfunction "EP_25") (pintype "input"))
      (node (ref "U9") (pin "2") (pinfunction "GND_2") (pintype "input"))
      (node (ref "U9") (pin "5") (pinfunction "REF_5") (pintype "input"))
      (node (ref "USB1") (pin "5") (pinfunction "GND_5") (pintype "input"))
    )
    (net (code "23") (name "GPIO0") (class "Default")
      (node (ref "C14") (pin "2") (pinfunction "2_2") (pintype "input"))
      (node (ref "Q2") (pin "3") (pinfunction "3_3") (pintype "unspecified"))
      (node (ref "SW2") (pin "2") (pinfunction "2_2") (pintype "input"))
      (node (ref "U1") (pin "27") (pinfunction "IO0_27") (pintype "unspecified"))
    )
    (net (code "24") (name "H1") (class "Default")
      (node (ref "U1") (pin "17") (pinfunction "IO9_17") (pintype "unspecified"))
      (node (ref "U5") (pin "2") (pinfunction "1A1_2") (pintype "input"))
    )
    (net (code "25") (name "H1CS") (class "Default")
      (node (ref "H1") (pin "1") (pinfunction "1_1") (pintype "input"))
      (node (ref "U9") (pin "1") (pinfunction "OUT_1") (pintype "input"))
    )
    (net (code "26") (name "H2") (class "Default")
      (node (ref "U1") (pin "19") (pinfunction "IO11_19") (pintype "unspecified"))
      (node (ref "U5") (pin "6") (pinfunction "1A3_6") (pintype "input"))
    )
    (net (code "27") (name "H2CS") (class "Default")
      (node (ref "H2") (pin "1") (pinfunction "1_1") (pintype "input"))
      (node (ref "U10") (pin "1") (pinfunction "OUT_1") (pintype "input"))
    )
    (net (code "28") (name "H3") (class "Default")
      (node (ref "U1") (pin "21") (pinfunction "IO13_21") (pintype "unspecified"))
      (node (ref "U5") (pin "11") (pinfunction "2A1_11") (pintype "input"))
    )
    (net (code "29") (name "H3CS") (class "Default")
      (node (ref "H3") (pin "1") (pinfunction "1_1") (pintype "input"))
      (node (ref "U11") (pin "1") (pinfunction "OUT_1") (pintype "input"))
    )
    (net (code "30") (name "H4") (class "Default")
      (node (ref "U1") (pin "8") (pinfunction "IO15_8") (pintype "unspecified"))
      (node (ref "U5") (pin "15") (pinfunction "2A3_15") (pintype "input"))
    )
    (net (code "31") (name "H4CS") (class "Default")
      (node (ref "H4") (pin "1") (pinfunction "1_1") (pintype "input"))
      (node (ref "U12") (pin "1") (pinfunction "OUT_1") (pintype "input"))
    )
    (net (code "32") (name "HAM1") (class "Default")
      (node (ref "L1") (pin "1") (pinfunction "1_1") (pintype "input"))
      (node (ref "U5") (pin "18") (pinfunction "1Y1_18") (pintype "input"))
    )
    (net (code "33") (name "HAM2") (class "Default")
      (node (ref "L2") (pin "1") (pinfunction "1_1") (pintype "input"))
      (node (ref "U5") (pin "14") (pinfunction "1Y3_14") (pintype "input"))
    )
    (net (code "34") (name "HAM3") (class "Default")
      (node (ref "L3") (pin "1") (pinfunction "1_1") (pintype "input"))
      (node (ref "U5") (pin "9") (pinfunction "2Y1_9") (pintype "input"))
    )
    (net (code "35") (name "HAM4") (class "Default")
      (node (ref "L4") (pin "1") (pinfunction "1_1") (pintype "input"))
      (node (ref "U5") (pin "5") (pinfunction "2Y3_5") (pintype "input"))
    )
    (net (code "36") (name "IN-1") (class "Default")
      (node (ref "L1") (pin "2") (pinfunction "2_2") (pintype "input"))
      (node (ref "R37") (pin "1") (pinfunction "1_1") (pintype "input"))
      (node (ref "U9") (pin "4") (pinfunction "IN-_4") (pintype "input"))
    )
    (net (code "37") (name "IN-2") (class "Default")
      (node (ref "L2") (pin "2") (pinfunction "2_2") (pintype "input"))
      (node (ref "R38") (pin "1") (pinfunction "1_1") (pintype "input"))
      (node (ref "U10") (pin "4") (pinfunction "IN-_4") (pintype "input"))
    )
    (net (code "38") (name "IN-3") (class "Default")
      (node (ref "L3") (pin "2") (pinfunction "2_2") (pintype "input"))
      (node (ref "R39") (pin "1") (pinfunction "1_1") (pintype "input"))
      (node (ref "U11") (pin "4") (pinfunction "IN-_4") (pintype "input"))
    )
    (net (code "39") (name "IN-4") (class "Default")
      (node (ref "L4") (pin "2") (pinfunction "2_2") (pintype "input"))
      (node (ref "R40") (pin "1") (pinfunction "1_1") (pintype "input"))
      (node (ref "U12") (pin "4") (pinfunction "IN-_4") (pintype "input"))
    )
    (net (code "40") (name "M+") (class "Default")
      (node (ref "J2") (pin "3") (pinfunction "3_3") (pintype "input"))
      (node (ref "M1") (pin "3") (pinfunction "3_3") (pintype "input"))
      (node (ref "M2") (pin "3") (pinfunction "3_3") (pintype "input"))
      (node (ref "M3") (pin "3") (pinfunction "3_3") (pintype "input"))
      (node (ref "M4") (pin "3") (pinfunction "3_3") (pintype "input"))
    )
    (net (code "41") (name "MDIR1") (class "Default")
      (node (ref "M1") (pin "4") (pinfunction "4_4") (pintype "input"))
      (node (ref "U6") (pin "18") (pinfunction "1Y1_18") (pintype "input"))
    )
    (net (code "42") (name "MDIR2") (class "Default")
      (node (ref "M2") (pin "4") (pinfunction "4_4") (pintype "input"))
      (node (ref "U6") (pin "16") (pinfunction "1Y2_16") (pintype "input"))
    )
    (net (code "43") (name "MDIR3") (class "Default")
      (node (ref "M3") (pin "4") (pinfunction "4_4") (pintype "input"))
      (node (ref "U6") (pin "14") (pinfunction "1Y3_14") (pintype "input"))
    )
    (net (code "44") (name "MDIR4") (class "Default")
      (node (ref "M4") (pin "4") (pinfunction "4_4") (pintype "input"))
      (node (ref "U6") (pin "12") (pinfunction "1Y4_12") (pintype "input"))
    )
    (net (code "45") (name "MESC1") (class "Default")
      (node (ref "M1") (pin "1") (pinfunction "1_1") (pintype "input"))
      (node (ref "U6") (pin "9") (pinfunction "2Y1_9") (pintype "input"))
    )
    (net (code "46") (name "MESC2") (class "Default")
      (node (ref "M2") (pin "1") (pinfunction "1_1") (pintype "input"))
      (node (ref "U6") (pin "7") (pinfunction "2Y2_7") (pintype "input"))
    )
    (net (code "47") (name "MESC3") (class "Default")
      (node (ref "M3") (pin "1") (pinfunction "1_1") (pintype "input"))
      (node (ref "U6") (pin "5") (pinfunction "2Y3_5") (pintype "input"))
    )
    (net (code "48") (name "MESC4") (class "Default")
      (node (ref "M4") (pin "1") (pinfunction "1_1") (pintype "input"))
      (node (ref "U6") (pin "3") (pinfunction "2Y4_3") (pintype "input"))
    )
    (net (code "49") (name "Net-(D1-A)") (class "Default")
      (node (ref "D1") (pin "2") (pinfunction "A_2") (pintype "input"))
      (node (ref "USB1") (pin "1") (pinfunction "VBUS_1") (pintype "input"))
    )
    (net (code "50") (name "Net-(J2-Pad2)") (class "Default")
      (node (ref "J2") (pin "2") (pinfunction "2_2") (pintype "input"))
      (node (ref "P1") (pin "1") (pinfunction "1_1") (pintype "input"))
    )
    (net (code "51") (name "Net-(J2-Pad4)") (class "Default")
      (node (ref "J2") (pin "4") (pinfunction "4_4") (pintype "input"))
      (node (ref "Q5") (pin "3") (pinfunction "3_3") (pintype "unspecified"))
    )
    (net (code "52") (name "Net-(LED3-Pad1)") (class "Default")
      (node (ref "LED3") (pin "1") (pinfunction "1_1") (pintype "input"))
      (node (ref "R7") (pin "1") (pinfunction "1_1") (pintype "input"))
    )
    (net (code "53") (name "Net-(LED4-Pad1)") (class "Default")
      (node (ref "LED4") (pin "1") (pinfunction "1_1") (pintype "input"))
      (node (ref "R6") (pin "1") (pinfunction "1_1") (pintype "input"))
    )
    (net (code "54") (name "Net-(LED5-A)") (class "Default")
      (node (ref "LED5") (pin "2") (pinfunction "A_2") (pintype "input"))
      (node (ref "R3") (pin "2") (pinfunction "2_2") (pintype "input"))
    )
    (net (code "55") (name "Net-(M1-Pad5)") (class "Default")
      (node (ref "M1") (pin "5") (pinfunction "5_5") (pintype "input"))
      (node (ref "R12") (pin "1") (pinfunction "1_1") (pintype "input"))
    )
    (net (code "56") (name "Net-(M2-Pad5)") (class "Default")
      (node (ref "M2") (pin "5") (pinfunction "5_5") (pintype "input"))
      (node (ref "R14") (pin "1") (pinfunction "1_1") (pintype "input"))
    )
    (net (code "57") (name "Net-(M3-Pad5)") (class "Default")
      (node (ref "M3") (pin "5") (pinfunction "5_5") (pintype "input"))
      (node (ref "R16") (pin "1") (pinfunction "1_1") (pintype "input"))
    )
    (net (code "58") (name "Net-(M4-Pad5)") (class "Default")
      (node (ref "M4") (pin "5") (pinfunction "5_5") (pintype "input"))
      (node (ref "R18") (pin "1") (pinfunction "1_1") (pintype "input"))
    )
    (net (code "59") (name "Net-(Q1-Pad1)") (class "Default")
      (node (ref "Q1") (pin "1") (pinfunction "1_1") (pintype "unspecified"))
      (node (ref "R4") (pin "2") (pinfunction "2_2") (pintype "input"))
    )
    (net (code "60") (name "Net-(Q2-Pad1)") (class "Default")
      (node (ref "Q2") (pin "1") (pinfunction "1_1") (pintype "unspecified"))
      (node (ref "R5") (pin "2") (pinfunction "2_2") (pintype "input"))
    )
    (net (code "61") (name "Net-(U1-IO4)") (class "Default")
      (node (ref "H1") (pin "2") (pinfunction "2_2") (pintype "input"))
      (node (ref "U1") (pin "4") (pinfunction "IO4_4") (pintype "unspecified"))
    )
    (net (code "62") (name "Net-(U1-IO5)") (class "Default")
      (node (ref "H2") (pin "2") (pinfunction "2_2") (pintype "input"))
      (node (ref "U1") (pin "5") (pinfunction "IO5_5") (pintype "unspecified"))
    )
    (net (code "63") (name "Net-(U1-IO6)") (class "Default")
      (node (ref "H3") (pin "2") (pinfunction "2_2") (pintype "input"))
      (node (ref "U1") (pin "6") (pinfunction "IO6_6") (pintype "unspecified"))
    )
    (net (code "64") (name "Net-(U1-IO7)") (class "Default")
      (node (ref "H4") (pin "2") (pinfunction "2_2") (pintype "input"))
      (node (ref "U1") (pin "7") (pinfunction "IO7_7") (pintype "unspecified"))
    )
    (net (code "65") (name "Net-(U8-AD0)") (class "Default")
      (node (ref "R22") (pin "2") (pinfunction "2_2") (pintype "input"))
      (node (ref "U8") (pin "9") (pinfunction "AD0_9") (pintype "input"))
    )
    (net (code "66") (name "Net-(U8-CPOUT)") (class "Default")
      (node (ref "C31") (pin "2") (pinfunction "2_2") (pintype "input"))
      (node (ref "U8") (pin "20") (pinfunction "CPOUT_20") (pintype "input"))
    )
    (net (code "67") (name "Net-(U8-REGOUT)") (class "Default")
      (node (ref "C32") (pin "2") (pinfunction "2_2") (pintype "input"))
      (node (ref "U8") (pin "10") (pinfunction "REGOUT_10") (pintype "input"))
    )
    (net (code "68") (name "Net-(U8-VDD)") (class "Default")
      (node (ref "C30") (pin "1") (pinfunction "1_1") (pintype "input"))
      (node (ref "R41") (pin "1") (pinfunction "1_1") (pintype "input"))
      (node (ref "U8") (pin "13") (pinfunction "VDD_13") (pintype "input"))
    )
    (net (code "69") (name "RTS") (class "Default")
      (node (ref "Q1") (pin "2") (pinfunction "2_2") (pintype "unspecified"))
      (node (ref "R5") (pin "1") (pinfunction "1_1") (pintype "input"))
      (node (ref "U3") (pin "14") (pinfunction "RTS#_14") (pintype "input"))
    )
    (net (code "70") (name "RXD0") (class "Default")
      (node (ref "LED4") (pin "2") (pinfunction "2_2") (pintype "input"))
      (node (ref "U1") (pin "36") (pinfunction "RXD0_36") (pintype "unspecified"))
      (node (ref "U3") (pin "2") (pinfunction "TXD_2") (pintype "input"))
    )
    (net (code "71") (name "RXD1") (class "Default")
      (node (ref "H5") (pin "3") (pinfunction "3_3") (pintype "input"))
      (node (ref "U1") (pin "11") (pinfunction "IO18_11") (pintype "unspecified"))
    )
    (net (code "72") (name "S1") (class "Default")
      (node (ref "U1") (pin "18") (pinfunction "IO10_18") (pintype "unspecified"))
      (node (ref "U5") (pin "4") (pinfunction "1A2_4") (pintype "input"))
    )
    (net (code "73") (name "S2") (class "Default")
      (node (ref "U1") (pin "20") (pinfunction "IO12_20") (pintype "unspecified"))
      (node (ref "U5") (pin "8") (pinfunction "1A4_8") (pintype "input"))
    )
    (net (code "74") (name "S3") (class "Default")
      (node (ref "U1") (pin "22") (pinfunction "IO14_22") (pintype "unspecified"))
      (node (ref "U5") (pin "13") (pinfunction "2A2_13") (pintype "input"))
    )
    (net (code "75") (name "S4") (class "Default")
      (node (ref "U1") (pin "9") (pinfunction "IO16_9") (pintype "unspecified"))
      (node (ref "U5") (pin "17") (pinfunction "2A4_17") (pintype "input"))
    )
    (net (code "76") (name "SCL0") (class "Default")
      (node (ref "R20") (pin "1") (pinfunction "1_1") (pintype "input"))
      (node (ref "U1") (pin "13") (pinfunction "IO19_13") (pintype "unspecified"))
      (node (ref "U8") (pin "23") (pinfunction "SCL_23") (pintype "input"))
    )
    (net (code "77") (name "SDA0") (class "Default")
      (node (ref "R21") (pin "1") (pinfunction "1_1") (pintype "input"))
      (node (ref "U1") (pin "14") (pinfunction "IO20_14") (pintype "unspecified"))
      (node (ref "U8") (pin "24") (pinfunction "SDA_24") (pintype "input"))
    )
    (net (code "78") (name "SH1") (class "Default")
      (node (ref "L1") (pin "4") (pinfunction "4_4") (pintype "input"))
      (node (ref "U5") (pin "16") (pinfunction "1Y2_16") (pintype "input"))
    )
    (net (code "79") (name "SH2") (class "Default")
      (node (ref "L2") (pin "4") (pinfunction "4_4") (pintype "input"))
      (node (ref "U5") (pin "12") (pinfunction "1Y4_12") (pintype "input"))
    )
    (net (code "80") (name "SH3") (class "Default")
      (node (ref "L3") (pin "4") (pinfunction "4_4") (pintype "input"))
      (node (ref "U5") (pin "7") (pinfunction "2Y2_7") (pintype "input"))
    )
    (net (code "81") (name "SH4") (class "Default")
      (node (ref "L4") (pin "4") (pinfunction "4_4") (pintype "input"))
      (node (ref "U5") (pin "3") (pinfunction "2Y4_3") (pintype "input"))
    )
    (net (code "82") (name "TEMP") (class "Default")
      (node (ref "R8") (pin "1") (pinfunction "1_1") (pintype "unspecified"))
      (node (ref "R9") (pin "2") (pinfunction "2_2") (pintype "input"))
      (node (ref "U1") (pin "39") (pinfunction "IO1_39") (pintype "unspecified"))
    )
    (net (code "83") (name "TXD0") (class "Default")
      (node (ref "LED3") (pin "2") (pinfunction "2_2") (pintype "input"))
      (node (ref "U1") (pin "37") (pinfunction "TXD0_37") (pintype "unspecified"))
      (node (ref "U3") (pin "3") (pinfunction "RXD_3") (pintype "input"))
    )
    (net (code "84") (name "TXD1") (class "Default")
      (node (ref "H5") (pin "4") (pinfunction "4_4") (pintype "input"))
      (node (ref "U1") (pin "10") (pinfunction "IO17_10") (pintype "unspecified"))
    )
    (net (code "85") (name "VBATT") (class "Default")
      (node (ref "C15") (pin "1") (pinfunction "1_1") (pintype "input"))
      (node (ref "R10") (pin "2") (pinfunction "2_2") (pintype "input"))
      (node (ref "R11") (pin "1") (pinfunction "1_1") (pintype "input"))
      (node (ref "U1") (pin "38") (pinfunction "IO2_38") (pintype "unspecified"))
    )
    (net (code "86") (name "unconnected-(M1-Pad2)") (class "Default")
      (node (ref "M1") (pin "2") (pinfunction "2_2") (pintype "input+no_connect"))
    )
    (net (code "87") (name "unconnected-(M2-Pad2)") (class "Default")
      (node (ref "M2") (pin "2") (pinfunction "2_2") (pintype "input+no_connect"))
    )
    (net (code "88") (name "unconnected-(M3-Pad2)") (class "Default")
      (node (ref "M3") (pin "2") (pinfunction "2_2") (pintype "input+no_connect"))
    )
    (net (code "89") (name "unconnected-(M4-Pad2)") (class "Default")
      (node (ref "M4") (pin "2") (pinfunction "2_2") (pintype "input+no_connect"))
    )
    (net (code "90") (name "unconnected-(U1-IO3-Pad15)") (class "Default")
      (node (ref "U1") (pin "15") (pinfunction "IO3_15") (pintype "unspecified+no_connect"))
    )
    (net (code "91") (name "unconnected-(U1-IO8-Pad12)") (class "Default")
      (node (ref "U1") (pin "12") (pinfunction "IO8_12") (pintype "unspecified+no_connect"))
    )
    (net (code "92") (name "unconnected-(U1-IO35-Pad28)") (class "Default")
      (node (ref "U1") (pin "28") (pinfunction "IO35_28") (pintype "unspecified+no_connect"))
    )
    (net (code "93") (name "unconnected-(U1-IO36-Pad29)") (class "Default")
      (node (ref "U1") (pin "29") (pinfunction "IO36_29") (pintype "unspecified+no_connect"))
    )
    (net (code "94") (name "unconnected-(U1-IO37-Pad30)") (class "Default")
      (node (ref "U1") (pin "30") (pinfunction "IO37_30") (pintype "unspecified+no_connect"))
    )
    (net (code "95") (name "unconnected-(U1-IO46-Pad16)") (class "Default")
      (node (ref "U1") (pin "16") (pinfunction "IO46_16") (pintype "unspecified+no_connect"))
    )
    (net (code "96") (name "unconnected-(U3-CTS#-Pad9)") (class "Default")
      (node (ref "U3") (pin "9") (pinfunction "CTS#_9") (pintype "input+no_connect"))
    )
    (net (code "97") (name "unconnected-(U3-DCD#-Pad12)") (class "Default")
      (node (ref "U3") (pin "12") (pinfunction "DCD#_12") (pintype "input+no_connect"))
    )
    (net (code "98") (name "unconnected-(U3-DSR#-Pad10)") (class "Default")
      (node (ref "U3") (pin "10") (pinfunction "DSR#_10") (pintype "input+no_connect"))
    )
    (net (code "99") (name "unconnected-(U3-R232-Pad15)") (class "Default")
      (node (ref "U3") (pin "15") (pinfunction "R232_15") (pintype "input+no_connect"))
    )
    (net (code "100") (name "unconnected-(U3-RI#-Pad11)") (class "Default")
      (node (ref "U3") (pin "11") (pinfunction "RI#_11") (pintype "input+no_connect"))
    )
    (net (code "101") (name "unconnected-(U3-X1-Pad7)") (class "Default")
      (node (ref "U3") (pin "7") (pinfunction "X1_7") (pintype "input+no_connect"))
    )
    (net (code "102") (name "unconnected-(U3-X2-Pad8)") (class "Default")
      (node (ref "U3") (pin "8") (pinfunction "X2_8") (pintype "input+no_connect"))
    )
    (net (code "103") (name "unconnected-(U8-AUX_CL-Pad7)") (class "Default")
      (node (ref "U8") (pin "7") (pinfunction "AUX_CL_7") (pintype "input+no_connect"))
    )
    (net (code "104") (name "unconnected-(U8-AUX_DA-Pad6)") (class "Default")
      (node (ref "U8") (pin "6") (pinfunction "AUX_DA_6") (pintype "input+no_connect"))
    )
    (net (code "105") (name "unconnected-(U8-INT-Pad12)") (class "Default")
      (node (ref "U8") (pin "12") (pinfunction "INT_12") (pintype "input+no_connect"))
    )
    (net (code "106") (name "unconnected-(U8-NC-Pad2)") (class "Default")
      (node (ref "U8") (pin "2") (pinfunction "NC_2") (pintype "input+no_connect"))
    )
    (net (code "107") (name "unconnected-(U8-NC-Pad3)") (class "Default")
      (node (ref "U8") (pin "3") (pinfunction "NC_3") (pintype "input+no_connect"))
    )
    (net (code "108") (name "unconnected-(U8-NC-Pad4)") (class "Default")
      (node (ref "U8") (pin "4") (pinfunction "NC_4") (pintype "input+no_connect"))
    )
    (net (code "109") (name "unconnected-(U8-NC-Pad5)") (class "Default")
      (node (ref "U8") (pin "5") (pinfunction "NC_5") (pintype "input+no_connect"))
    )
    (net (code "110") (name "unconnected-(U8-NC-Pad14)") (class "Default")
      (node (ref "U8") (pin "14") (pinfunction "NC_14") (pintype "input+no_connect"))
    )
    (net (code "111") (name "unconnected-(U8-NC-Pad15)") (class "Default")
      (node (ref "U8") (pin "15") (pinfunction "NC_15") (pintype "input+no_connect"))
    )
    (net (code "112") (name "unconnected-(U8-NC-Pad16)") (class "Default")
      (node (ref "U8") (pin "16") (pinfunction "NC_16") (pintype "input+no_connect"))
    )
    (net (code "113") (name "unconnected-(U8-NC-Pad17)") (class "Default")
      (node (ref "U8") (pin "17") (pinfunction "NC_17") (pintype "input+no_connect"))
    )
    (net (code "114") (name "unconnected-(U8-RESV-Pad19)") (class "Default")
      (node (ref "U8") (pin "19") (pinfunction "RESV_19") (pintype "input+no_connect"))
    )
    (net (code "115") (name "unconnected-(U8-RESV-Pad21)") (class "Default")
      (node (ref "U8") (pin "21") (pinfunction "RESV_21") (pintype "input+no_connect"))
    )
    (net (code "116") (name "unconnected-(U8-RESV-Pad22)") (class "Default")
      (node (ref "U8") (pin "22") (pinfunction "RESV_22") (pintype "input+no_connect"))
    )
    (net (code "117") (name "unconnected-(USB1-ID-Pad4)") (class "Default")
      (node (ref "USB1") (pin "4") (pinfunction "ID_4") (pintype "input+no_connect"))
    )
  )
)
